# T6.net
KiCad netlist of a schematic drawn in Altium Designer
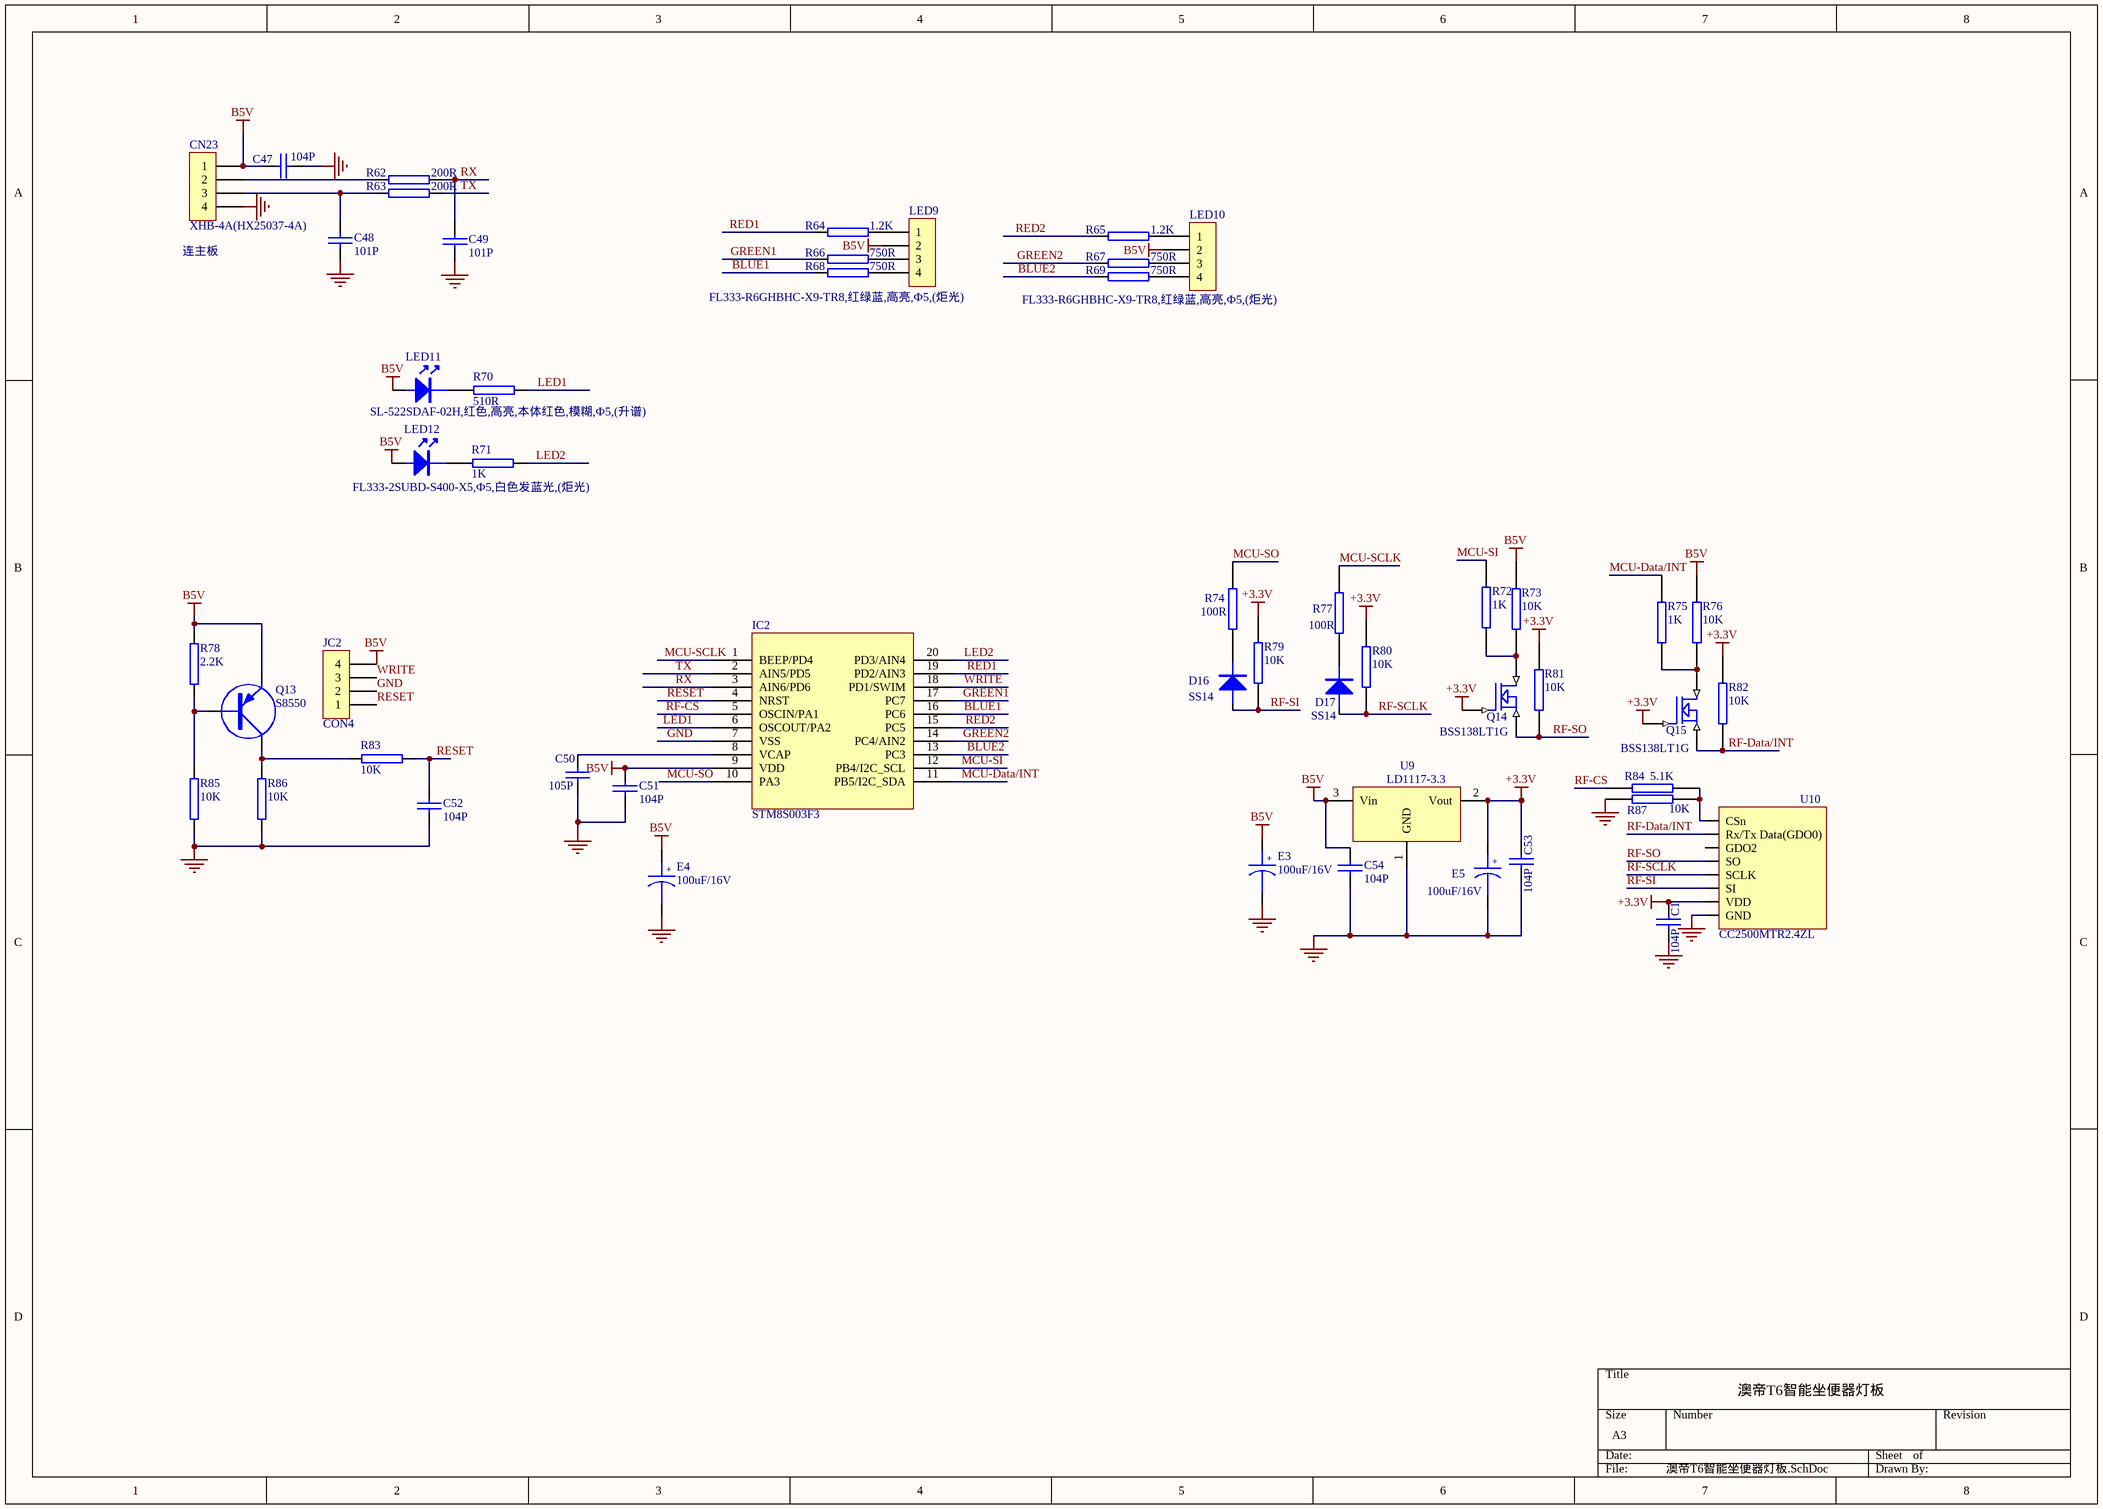
[diagram p0: 澳帝T6智能坐便器灯板.SchDoc]

(export (version "E")
  (design (tool "Eeschema 10.0.6"))
  (components
    (comp (ref "C1")
      (value "104P")
      (footprint "C0603-T")
      (description "Capacitor")
      (libsource (lib "") (part "CAP_1"))
    )
    (comp (ref "C47")
      (value "104P")
      (footprint "C0603-T")
      (description "Capacitor")
      (libsource (lib "*") (part "CAP"))
    )
    (comp (ref "C48")
      (value "101P")
      (footprint "C0603-T")
      (description "Capacitor")
      (libsource (lib "*") (part "CAP"))
    )
    (comp (ref "C49")
      (value "101P")
      (footprint "C0603-T")
      (description "Capacitor")
      (libsource (lib "*") (part "CAP"))
    )
    (comp (ref "C50")
      (value "105P")
      (footprint "C0603-T")
      (description "Capacitor")
      (libsource (lib "*") (part "CAP"))
    )
    (comp (ref "C51")
      (value "104P")
      (footprint "C0603-T")
      (description "Capacitor")
      (libsource (lib "*") (part "CAP"))
    )
    (comp (ref "C52")
      (value "104P")
      (footprint "C0603-T")
      (description "Capacitor")
      (libsource (lib "*") (part "CAP"))
    )
    (comp (ref "C53")
      (value "104P")
      (footprint "C0603-T")
      (description "Capacitor")
      (libsource (lib "") (part "CAP_1"))
    )
    (comp (ref "C54")
      (value "104P")
      (footprint "C0603-T")
      (description "Capacitor")
      (libsource (lib "") (part "CAP_1"))
    )
    (comp (ref "CN23")
      (value "XHB-4A(HX25037-4A)")
      (footprint "SMW250-04")
      (description "Connector")
      (libsource (lib "") (part "CON4_1"))
    )
    (comp (ref "D16")
      (value "SS14")
      (footprint "D-SMA-T")
      (description "Diode")
      (libsource (lib "*") (part "DIODE"))
    )
    (comp (ref "D17")
      (value "SS14")
      (footprint "D-SMA-T")
      (description "Diode")
      (libsource (lib "*") (part "DIODE"))
    )
    (comp (ref "E3")
      (value "100uF/16V")
      (footprint "E2.5-5-A-SI")
      (description "Capacitor")
      (libsource (lib "*") (part "CAPACITOR POL"))
    )
    (comp (ref "E4")
      (value "100uF/16V")
      (footprint "E2.5-5-A-SI")
      (description "Capacitor")
      (libsource (lib "*") (part "CAPACITOR POL"))
    )
    (comp (ref "E5")
      (value "100uF/16V")
      (footprint "E2.5-5-A-SI")
      (description "Capacitor")
      (libsource (lib "*") (part "CAPACITOR POL"))
    )
    (comp (ref "IC2")
      (value "STM8S003F3")
      (footprint "SOP20-4.5-0.65")
      (libsource (lib "*") (part "Component_1"))
    )
    (comp (ref "JC2")
      (value "CON4")
      (footprint "PZ-1*4-M-SI")
      (description "Connector")
      (libsource (lib "*") (part "CON4"))
    )
    (comp (ref "LED9")
      (value "FL333-R6GHBHC-X9-TR8,红绿蓝,高亮,Ф5,(炬光)")
      (footprint "LED-RGB01")
      (description "Connector")
      (libsource (lib "DFsch14-DF") (part "CON4"))
    )
    (comp (ref "LED10")
      (value "FL333-R6GHBHC-X9-TR8,红绿蓝,高亮,Ф5,(炬光)")
      (footprint "LED-RGB01")
      (description "Connector")
      (libsource (lib "DFsch14-DF") (part "CON4"))
    )
    (comp (ref "LED11")
      (value "SL-522SDAF-02H,红色,高亮,本体红色,模糊,Ф5,(升谱)")
      (footprint "LED-2.5-D5-A")
      (libsource (lib "DFsch14-DF") (part "DIODE-LED*1"))
    )
    (comp (ref "LED12")
      (value "FL333-2SUBD-S400-X5,Ф5,白色发蓝光,(炬光)")
      (footprint "LED-2.5-D5-A")
      (libsource (lib "DFsch14-DF") (part "DIODE-LED*1"))
    )
    (comp (ref "Q13")
      (value "S8550")
      (footprint "SOT23-123-T")
      (description "PNP Transistor")
      (libsource (lib "*") (part "PNP"))
    )
    (comp (ref "Q14") (value "BSS138LT1G") (footprint "SOT23-123-T") (libsource (lib "*") (part "MOSFET N")))
    (comp (ref "Q15") (value "BSS138LT1G") (footprint "SOT23-123-T") (libsource (lib "*") (part "MOSFET N")))
    (comp (ref "R62") (value "200R") (footprint "R0603-T") (libsource (lib "*") (part "RES2")))
    (comp (ref "R63") (value "200R") (footprint "R0603-T") (libsource (lib "*") (part "RES2")))
    (comp (ref "R64") (value "1.2K") (footprint "R0603-T") (libsource (lib "*") (part "RES2")))
    (comp (ref "R65") (value "1.2K") (footprint "R0603-T") (libsource (lib "*") (part "RES2")))
    (comp (ref "R66") (value "750R") (footprint "R0603-T") (libsource (lib "*") (part "RES2")))
    (comp (ref "R67") (value "750R") (footprint "R0603-T") (libsource (lib "*") (part "RES2")))
    (comp (ref "R68") (value "750R") (footprint "R0603-T") (libsource (lib "*") (part "RES2")))
    (comp (ref "R69") (value "750R") (footprint "R0603-T") (libsource (lib "*") (part "RES2")))
    (comp (ref "R70") (value "510R") (footprint "R0603-T") (libsource (lib "*") (part "RES2")))
    (comp (ref "R71") (value "1K") (footprint "R0603-T") (libsource (lib "*") (part "RES2")))
    (comp (ref "R72") (value "1K") (footprint "R0603-T") (libsource (lib "") (part "RES2_1")))
    (comp (ref "R73") (value "10K") (footprint "R0603-T") (libsource (lib "") (part "RES2_1")))
    (comp (ref "R74") (value "100R") (footprint "R0603-T") (libsource (lib "") (part "RES2_1")))
    (comp (ref "R75") (value "1K") (footprint "R0603-T") (libsource (lib "") (part "RES2_1")))
    (comp (ref "R76") (value "10K") (footprint "R0603-T") (libsource (lib "") (part "RES2_1")))
    (comp (ref "R77") (value "100R") (footprint "R0603-T") (libsource (lib "") (part "RES2_1")))
    (comp (ref "R78") (value "2.2K") (footprint "R0603-T") (libsource (lib "*") (part "RES2")))
    (comp (ref "R79") (value "10K") (footprint "R0603-T") (libsource (lib "") (part "RES2_1")))
    (comp (ref "R80") (value "10K") (footprint "R0603-T") (libsource (lib "") (part "RES2_1")))
    (comp (ref "R81") (value "10K") (footprint "R0603-T") (libsource (lib "") (part "RES2_1")))
    (comp (ref "R82") (value "10K") (footprint "R0603-T") (libsource (lib "") (part "RES2_1")))
    (comp (ref "R83") (value "10K") (footprint "R0603-T") (libsource (lib "*") (part "RES2")))
    (comp (ref "R84") (value "5.1K") (footprint "R0603-T") (libsource (lib "") (part "RES2_2")))
    (comp (ref "R85") (value "10K") (footprint "R0603-T") (libsource (lib "*") (part "RES2")))
    (comp (ref "R86") (value "10K") (footprint "R0603-T") (libsource (lib "*") (part "RES2")))
    (comp (ref "R87") (value "10K") (footprint "R0603-T") (libsource (lib "") (part "RES2_2")))
    (comp (ref "U9") (value "LD1117-3.3") (footprint "SOT223-T") (libsource (lib "*") (part "VOLTREG")))
    (comp (ref "U10")
      (value "CC2500MTR2.4ZL")
      (footprint "CC2500MTR2.4ZL")
      (libsource (lib "*") (part "2.4GRF"))
    )
  )
  (nets
    (net (code "1") (name "+3.3V") (class "Default")
      (node (ref "C1") (pin "2") (pinfunction "2_2") (pintype "passive"))
      (node (ref "C53") (pin "2") (pinfunction "2_2") (pintype "passive"))
      (node (ref "E5") (pin "1") (pinfunction "1_1") (pintype "passive"))
      (node (ref "Q14") (pin "1") (pinfunction "G_1") (pintype "input"))
      (node (ref "Q15") (pin "1") (pinfunction "G_1") (pintype "input"))
      (node (ref "R79") (pin "2") (pinfunction "2_2") (pintype "passive"))
      (node (ref "R80") (pin "2") (pinfunction "2_2") (pintype "passive"))
      (node (ref "R81") (pin "2") (pinfunction "2_2") (pintype "passive"))
      (node (ref "R82") (pin "1") (pinfunction "1_1") (pintype "passive"))
      (node (ref "U10") (pin "2") (pinfunction "VDD_2") (pintype "passive"))
      (node (ref "U9") (pin "2") (pinfunction "Vout_2") (pintype "passive"))
    )
    (net (code "2") (name "/BLUE1") (class "Default")
      (node (ref "IC2") (pin "16") (pinfunction "PC6_16") (pintype "passive"))
      (node (ref "R68") (pin "2") (pinfunction "2_2") (pintype "passive"))
    )
    (net (code "3") (name "/BLUE2") (class "Default")
      (node (ref "IC2") (pin "13") (pinfunction "PC3_13") (pintype "passive"))
      (node (ref "R69") (pin "2") (pinfunction "2_2") (pintype "passive"))
    )
    (net (code "4") (name "/GREEN1") (class "Default")
      (node (ref "IC2") (pin "17") (pinfunction "PC7_17") (pintype "passive"))
      (node (ref "R66") (pin "2") (pinfunction "2_2") (pintype "passive"))
    )
    (net (code "5") (name "/GREEN2") (class "Default")
      (node (ref "IC2") (pin "14") (pinfunction "PC4/AIN2_14") (pintype "passive"))
      (node (ref "R67") (pin "2") (pinfunction "2_2") (pintype "passive"))
    )
    (net (code "6") (name "/LED1") (class "Default")
      (node (ref "IC2") (pin "6") (pinfunction "OSCOUT/PA2_6") (pintype "passive"))
      (node (ref "R70") (pin "1") (pinfunction "1_1") (pintype "passive"))
    )
    (net (code "7") (name "/LED2") (class "Default")
      (node (ref "IC2") (pin "20") (pinfunction "PD3/AIN4_20") (pintype "passive"))
      (node (ref "R71") (pin "1") (pinfunction "1_1") (pintype "passive"))
    )
    (net (code "8") (name "/MCU-Data{slash}INT") (class "Default")
      (node (ref "IC2") (pin "11") (pinfunction "PB5/I2C_SDA_11") (pintype "passive"))
      (node (ref "R75") (pin "1") (pinfunction "1_1") (pintype "passive"))
    )
    (net (code "9") (name "/MCU-SCLK") (class "Default")
      (node (ref "IC2") (pin "1") (pinfunction "BEEP/PD4_1") (pintype "passive"))
      (node (ref "R77") (pin "2") (pinfunction "2_2") (pintype "passive"))
    )
    (net (code "10") (name "/MCU-SI") (class "Default")
      (node (ref "IC2") (pin "12") (pinfunction "PB4/I2C_SCL_12") (pintype "passive"))
      (node (ref "R72") (pin "1") (pinfunction "1_1") (pintype "passive"))
    )
    (net (code "11") (name "/MCU-SO") (class "Default")
      (node (ref "IC2") (pin "10") (pinfunction "PA3_10") (pintype "passive"))
      (node (ref "R74") (pin "1") (pinfunction "1_1") (pintype "passive"))
    )
    (net (code "12") (name "/RED1") (class "Default")
      (node (ref "IC2") (pin "19") (pinfunction "PD2/AIN3_19") (pintype "passive"))
      (node (ref "R64") (pin "2") (pinfunction "2_2") (pintype "passive"))
    )
    (net (code "13") (name "/RED2") (class "Default")
      (node (ref "IC2") (pin "15") (pinfunction "PC5_15") (pintype "passive"))
      (node (ref "R65") (pin "2") (pinfunction "2_2") (pintype "passive"))
    )
    (net (code "14") (name "/RESET") (class "Default")
      (node (ref "C52") (pin "2") (pinfunction "2_2") (pintype "passive"))
      (node (ref "IC2") (pin "4") (pinfunction "NRST_4") (pintype "passive"))
      (node (ref "JC2") (pin "1") (pinfunction "1_1") (pintype "passive"))
      (node (ref "R83") (pin "1") (pinfunction "1_1") (pintype "passive"))
    )
    (net (code "15") (name "/RF-CS") (class "Default")
      (node (ref "IC2") (pin "5") (pinfunction "OSCIN/PA1_5") (pintype "passive"))
      (node (ref "R84") (pin "2") (pinfunction "2_2") (pintype "passive"))
    )
    (net (code "16") (name "/RF-Data{slash}INT") (class "Default")
      (node (ref "Q15") (pin "2") (pinfunction "S_2") (pintype "input"))
      (node (ref "R82") (pin "2") (pinfunction "2_2") (pintype "passive"))
      (node (ref "U10") (pin "7") (pinfunction "Rx/Tx_Data(GDO0)_7") (pintype "passive"))
    )
    (net (code "17") (name "/RF-SCLK") (class "Default")
      (node (ref "D17") (pin "A") (pinfunction "A_A") (pintype "passive"))
      (node (ref "R80") (pin "1") (pinfunction "1_1") (pintype "passive"))
      (node (ref "U10") (pin "4") (pinfunction "SCLK_4") (pintype "passive"))
    )
    (net (code "18") (name "/RF-SI") (class "Default")
      (node (ref "D16") (pin "A") (pinfunction "A_A") (pintype "passive"))
      (node (ref "R79") (pin "1") (pinfunction "1_1") (pintype "passive"))
      (node (ref "U10") (pin "3") (pinfunction "SI_3") (pintype "passive"))
    )
    (net (code "19") (name "/RF-SO") (class "Default")
      (node (ref "Q14") (pin "2") (pinfunction "S_2") (pintype "input"))
      (node (ref "R81") (pin "1") (pinfunction "1_1") (pintype "passive"))
      (node (ref "U10") (pin "5") (pinfunction "SO_5") (pintype "passive"))
    )
    (net (code "20") (name "/RX") (class "Default")
      (node (ref "C49") (pin "1") (pinfunction "1_1") (pintype "passive"))
      (node (ref "IC2") (pin "3") (pinfunction "AIN6/PD6_3") (pintype "passive"))
      (node (ref "R62") (pin "1") (pinfunction "1_1") (pintype "passive"))
    )
    (net (code "21") (name "/TX") (class "Default")
      (node (ref "IC2") (pin "2") (pinfunction "AIN5/PD5_2") (pintype "passive"))
      (node (ref "R63") (pin "1") (pinfunction "1_1") (pintype "passive"))
    )
    (net (code "22") (name "/WRITE") (class "Default")
      (node (ref "IC2") (pin "18") (pinfunction "PD1/SWIM_18") (pintype "passive"))
      (node (ref "JC2") (pin "3") (pinfunction "3_3") (pintype "passive"))
    )
    (net (code "23") (name "B5V") (class "Default")
      (node (ref "C47") (pin "2") (pinfunction "2_2") (pintype "passive"))
      (node (ref "C51") (pin "1") (pinfunction "1_1") (pintype "passive"))
      (node (ref "C54") (pin "2") (pinfunction "2_2") (pintype "passive"))
      (node (ref "CN23") (pin "1") (pinfunction "1_1") (pintype "passive"))
      (node (ref "E3") (pin "1") (pinfunction "1_1") (pintype "passive"))
      (node (ref "E4") (pin "1") (pinfunction "1_1") (pintype "passive"))
      (node (ref "IC2") (pin "9") (pinfunction "VDD_9") (pintype "passive"))
      (node (ref "JC2") (pin "4") (pinfunction "4_4") (pintype "passive"))
      (node (ref "LED10") (pin "2") (pinfunction "2_2") (pintype "passive"))
      (node (ref "LED11") (pin "A") (pinfunction "A_A") (pintype "passive"))
      (node (ref "LED12") (pin "A") (pinfunction "A_A") (pintype "passive"))
      (node (ref "LED9") (pin "2") (pinfunction "2_2") (pintype "passive"))
      (node (ref "Q13") (pin "2") (pinfunction "E_2") (pintype "passive"))
      (node (ref "R73") (pin "2") (pinfunction "2_2") (pintype "passive"))
      (node (ref "R76") (pin "1") (pinfunction "1_1") (pintype "passive"))
      (node (ref "R78") (pin "2") (pinfunction "2_2") (pintype "passive"))
      (node (ref "U9") (pin "3") (pinfunction "Vin_3") (pintype "passive"))
    )
    (net (code "24") (name "GND") (class "Default")
      (node (ref "C1") (pin "1") (pinfunction "1_1") (pintype "passive"))
      (node (ref "C47") (pin "1") (pinfunction "1_1") (pintype "passive"))
      (node (ref "C48") (pin "2") (pinfunction "2_2") (pintype "passive"))
      (node (ref "C49") (pin "2") (pinfunction "2_2") (pintype "passive"))
      (node (ref "C50") (pin "2") (pinfunction "2_2") (pintype "passive"))
      (node (ref "C51") (pin "2") (pinfunction "2_2") (pintype "passive"))
      (node (ref "C52") (pin "1") (pinfunction "1_1") (pintype "passive"))
      (node (ref "C53") (pin "1") (pinfunction "1_1") (pintype "passive"))
      (node (ref "C54") (pin "1") (pinfunction "1_1") (pintype "passive"))
      (node (ref "CN23") (pin "4") (pinfunction "4_4") (pintype "passive"))
      (node (ref "E3") (pin "2") (pinfunction "2_2") (pintype "passive"))
      (node (ref "E4") (pin "2") (pinfunction "2_2") (pintype "passive"))
      (node (ref "E5") (pin "2") (pinfunction "2_2") (pintype "passive"))
      (node (ref "IC2") (pin "7") (pinfunction "VSS_7") (pintype "passive"))
      (node (ref "JC2") (pin "2") (pinfunction "2_2") (pintype "passive"))
      (node (ref "R85") (pin "1") (pinfunction "1_1") (pintype "passive"))
      (node (ref "R86") (pin "1") (pinfunction "1_1") (pintype "passive"))
      (node (ref "R87") (pin "2") (pinfunction "2_2") (pintype "passive"))
      (node (ref "U10") (pin "1") (pinfunction "GND_1") (pintype "passive"))
      (node (ref "U9") (pin "1") (pinfunction "GND_1") (pintype "passive"))
    )
    (net (code "25") (name "Net-(C48-Pad1)") (class "Default")
      (node (ref "C48") (pin "1") (pinfunction "1_1") (pintype "passive"))
      (node (ref "CN23") (pin "3") (pinfunction "3_3") (pintype "passive"))
      (node (ref "R63") (pin "2") (pinfunction "2_2") (pintype "passive"))
    )
    (net (code "26") (name "Net-(CN23-Pad2)") (class "Default")
      (node (ref "CN23") (pin "2") (pinfunction "2_2") (pintype "passive"))
      (node (ref "R62") (pin "2") (pinfunction "2_2") (pintype "passive"))
    )
    (net (code "27") (name "Net-(D16-PadK)") (class "Default")
      (node (ref "D16") (pin "K") (pinfunction "K_K") (pintype "passive"))
      (node (ref "R74") (pin "2") (pinfunction "2_2") (pintype "passive"))
    )
    (net (code "28") (name "Net-(D17-PadK)") (class "Default")
      (node (ref "D17") (pin "K") (pinfunction "K_K") (pintype "passive"))
      (node (ref "R77") (pin "1") (pinfunction "1_1") (pintype "passive"))
    )
    (net (code "29") (name "Net-(IC2-VCAP)") (class "Default")
      (node (ref "C50") (pin "1") (pinfunction "1_1") (pintype "passive"))
      (node (ref "IC2") (pin "8") (pinfunction "VCAP_8") (pintype "passive"))
    )
    (net (code "30") (name "Net-(LED9-Pad1)") (class "Default")
      (node (ref "LED9") (pin "1") (pinfunction "1_1") (pintype "passive"))
      (node (ref "R64") (pin "1") (pinfunction "1_1") (pintype "passive"))
    )
    (net (code "31") (name "Net-(LED9-Pad3)") (class "Default")
      (node (ref "LED9") (pin "3") (pinfunction "3_3") (pintype "passive"))
      (node (ref "R66") (pin "1") (pinfunction "1_1") (pintype "passive"))
    )
    (net (code "32") (name "Net-(LED9-Pad4)") (class "Default")
      (node (ref "LED9") (pin "4") (pinfunction "4_4") (pintype "passive"))
      (node (ref "R68") (pin "1") (pinfunction "1_1") (pintype "passive"))
    )
    (net (code "33") (name "Net-(LED10-Pad1)") (class "Default")
      (node (ref "LED10") (pin "1") (pinfunction "1_1") (pintype "passive"))
      (node (ref "R65") (pin "1") (pinfunction "1_1") (pintype "passive"))
    )
    (net (code "34") (name "Net-(LED10-Pad3)") (class "Default")
      (node (ref "LED10") (pin "3") (pinfunction "3_3") (pintype "passive"))
      (node (ref "R67") (pin "1") (pinfunction "1_1") (pintype "passive"))
    )
    (net (code "35") (name "Net-(LED10-Pad4)") (class "Default")
      (node (ref "LED10") (pin "4") (pinfunction "4_4") (pintype "passive"))
      (node (ref "R69") (pin "1") (pinfunction "1_1") (pintype "passive"))
    )
    (net (code "36") (name "Net-(LED11-PadK)") (class "Default")
      (node (ref "LED11") (pin "K") (pinfunction "K_K") (pintype "passive"))
      (node (ref "R70") (pin "2") (pinfunction "2_2") (pintype "passive"))
    )
    (net (code "37") (name "Net-(LED12-PadK)") (class "Default")
      (node (ref "LED12") (pin "K") (pinfunction "K_K") (pintype "passive"))
      (node (ref "R71") (pin "2") (pinfunction "2_2") (pintype "passive"))
    )
    (net (code "38") (name "Net-(Q13-B)") (class "Default")
      (node (ref "Q13") (pin "1") (pinfunction "B_1") (pintype "passive"))
      (node (ref "R78") (pin "1") (pinfunction "1_1") (pintype "passive"))
      (node (ref "R85") (pin "2") (pinfunction "2_2") (pintype "passive"))
    )
    (net (code "39") (name "Net-(Q13-C)") (class "Default")
      (node (ref "Q13") (pin "3") (pinfunction "C_3") (pintype "passive"))
      (node (ref "R83") (pin "2") (pinfunction "2_2") (pintype "passive"))
      (node (ref "R86") (pin "2") (pinfunction "2_2") (pintype "passive"))
    )
    (net (code "40") (name "Net-(Q14-D)") (class "Default")
      (node (ref "Q14") (pin "3") (pinfunction "D_3") (pintype "input"))
      (node (ref "R72") (pin "2") (pinfunction "2_2") (pintype "passive"))
      (node (ref "R73") (pin "1") (pinfunction "1_1") (pintype "passive"))
    )
    (net (code "41") (name "Net-(Q15-D)") (class "Default")
      (node (ref "Q15") (pin "3") (pinfunction "D_3") (pintype "input"))
      (node (ref "R75") (pin "2") (pinfunction "2_2") (pintype "passive"))
      (node (ref "R76") (pin "2") (pinfunction "2_2") (pintype "passive"))
    )
    (net (code "42") (name "Net-(U10-CSn)") (class "Default")
      (node (ref "R84") (pin "1") (pinfunction "1_1") (pintype "passive"))
      (node (ref "R87") (pin "1") (pinfunction "1_1") (pintype "passive"))
      (node (ref "U10") (pin "8") (pinfunction "CSn_8") (pintype "passive"))
    )
    (net (code "43") (name "unconnected-(U10-GDO2-Pad6)") (class "Default")
      (node (ref "U10") (pin "6") (pinfunction "GDO2_6") (pintype "passive"))
    )
  )
)
